# Relay_IO.net
KiCad netlist of a schematic drawn in Altium Designer
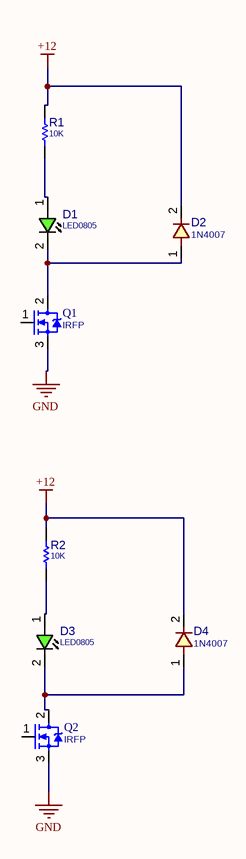
[diagram p0: Relay_IO.SchDoc]

(export (version "E")
  (design (tool "Eeschema 10.0.6"))
  (components
    (comp (ref "D1")
      (value "LED0805")
      (footprint "LED0805")
      (description "LED, SMD, 0805")
      (fields (field (name "MANF") "MANF") (field (name "MANF_P#") "MANF_PART#"))
      (libsource (lib "led(diode)") (part "LED_SMD_0805"))
    )
    (comp (ref "D2")
      (value "1N4007")
      (footprint "D_SMA")
      (description "DIODE, GENERAL PURPOSE, 1000V/1A")
      (fields (field (name "MANF") "Kingtronics") (field (name "MANF_P#") "M7"))
      (libsource (lib "diode") (part "DIODE_SMD_1N4007"))
    )
    (comp (ref "D3")
      (value "LED0805")
      (footprint "LED0805")
      (description "LED, SMD, 0805")
      (fields (field (name "MANF") "MANF") (field (name "MANF_P#") "MANF_PART#"))
      (libsource (lib "led(diode)") (part "LED_SMD_0805"))
    )
    (comp (ref "D4")
      (value "1N4007")
      (footprint "D_SMA")
      (description "DIODE, GENERAL PURPOSE, 1000V/1A")
      (fields (field (name "MANF") "Kingtronics") (field (name "MANF_P#") "M7"))
      (libsource (lib "diode") (part "DIODE_SMD_1N4007"))
    )
    (comp (ref "Q1")
      (value "IRFP")
      (footprint "TO247_3")
      (libsource (lib "transistor_fet") (part "MOSN_IRFP"))
    )
    (comp (ref "Q2")
      (value "IRFP")
      (footprint "TO247_3")
      (libsource (lib "transistor_fet") (part "MOSN_IRFP"))
    )
    (comp (ref "R1")
      (value "10K")
      (footprint "R0805")
      (description "RESISTOR, SMD")
      (libsource (lib "passive_smd") (part "RES_SMD_0805"))
    )
    (comp (ref "R2")
      (value "10K")
      (footprint "R0805")
      (description "RESISTOR, SMD")
      (libsource (lib "passive_smd") (part "RES_SMD_0805"))
    )
  )
  (nets
    (net (code "1") (name "+12") (class "Default")
      (node (ref "D2") (pin "2") (pinfunction "2_2") (pintype "passive"))
      (node (ref "D4") (pin "2") (pinfunction "2_2") (pintype "passive"))
      (node (ref "R1") (pin "2") (pinfunction "2_2") (pintype "passive"))
      (node (ref "R2") (pin "2") (pinfunction "2_2") (pintype "passive"))
    )
    (net (code "2") (name "GND") (class "Default")
      (node (ref "Q1") (pin "3") (pinfunction "S_3") (pintype "passive"))
      (node (ref "Q2") (pin "3") (pinfunction "S_3") (pintype "passive"))
    )
    (net (code "3") (name "Net-(D1-ANODE)") (class "Default")
      (node (ref "D1") (pin "1") (pinfunction "ANODE_1") (pintype "passive"))
      (node (ref "R1") (pin "1") (pinfunction "1_1") (pintype "passive"))
    )
    (net (code "4") (name "Net-(D1-CATHODE)") (class "Default")
      (node (ref "D1") (pin "2") (pinfunction "CATHODE_2") (pintype "passive"))
      (node (ref "D2") (pin "1") (pinfunction "1_1") (pintype "passive"))
      (node (ref "Q1") (pin "2") (pinfunction "D_2") (pintype "passive"))
    )
    (net (code "5") (name "Net-(D3-ANODE)") (class "Default")
      (node (ref "D3") (pin "1") (pinfunction "ANODE_1") (pintype "passive"))
      (node (ref "R2") (pin "1") (pinfunction "1_1") (pintype "passive"))
    )
    (net (code "6") (name "Net-(D3-CATHODE)") (class "Default")
      (node (ref "D3") (pin "2") (pinfunction "CATHODE_2") (pintype "passive"))
      (node (ref "D4") (pin "1") (pinfunction "1_1") (pintype "passive"))
      (node (ref "Q2") (pin "2") (pinfunction "D_2") (pintype "passive"))
    )
    (net (code "7") (name "unconnected-(Q1-G-Pad1)") (class "Default")
      (node (ref "Q1") (pin "1") (pinfunction "G_1") (pintype "passive"))
    )
    (net (code "8") (name "unconnected-(Q2-G-Pad1)") (class "Default")
      (node (ref "Q2") (pin "1") (pinfunction "G_1") (pintype "passive"))
    )
  )
)
